# BTB_Mezzanine.net
KiCad netlist of a schematic drawn in Altium Designer
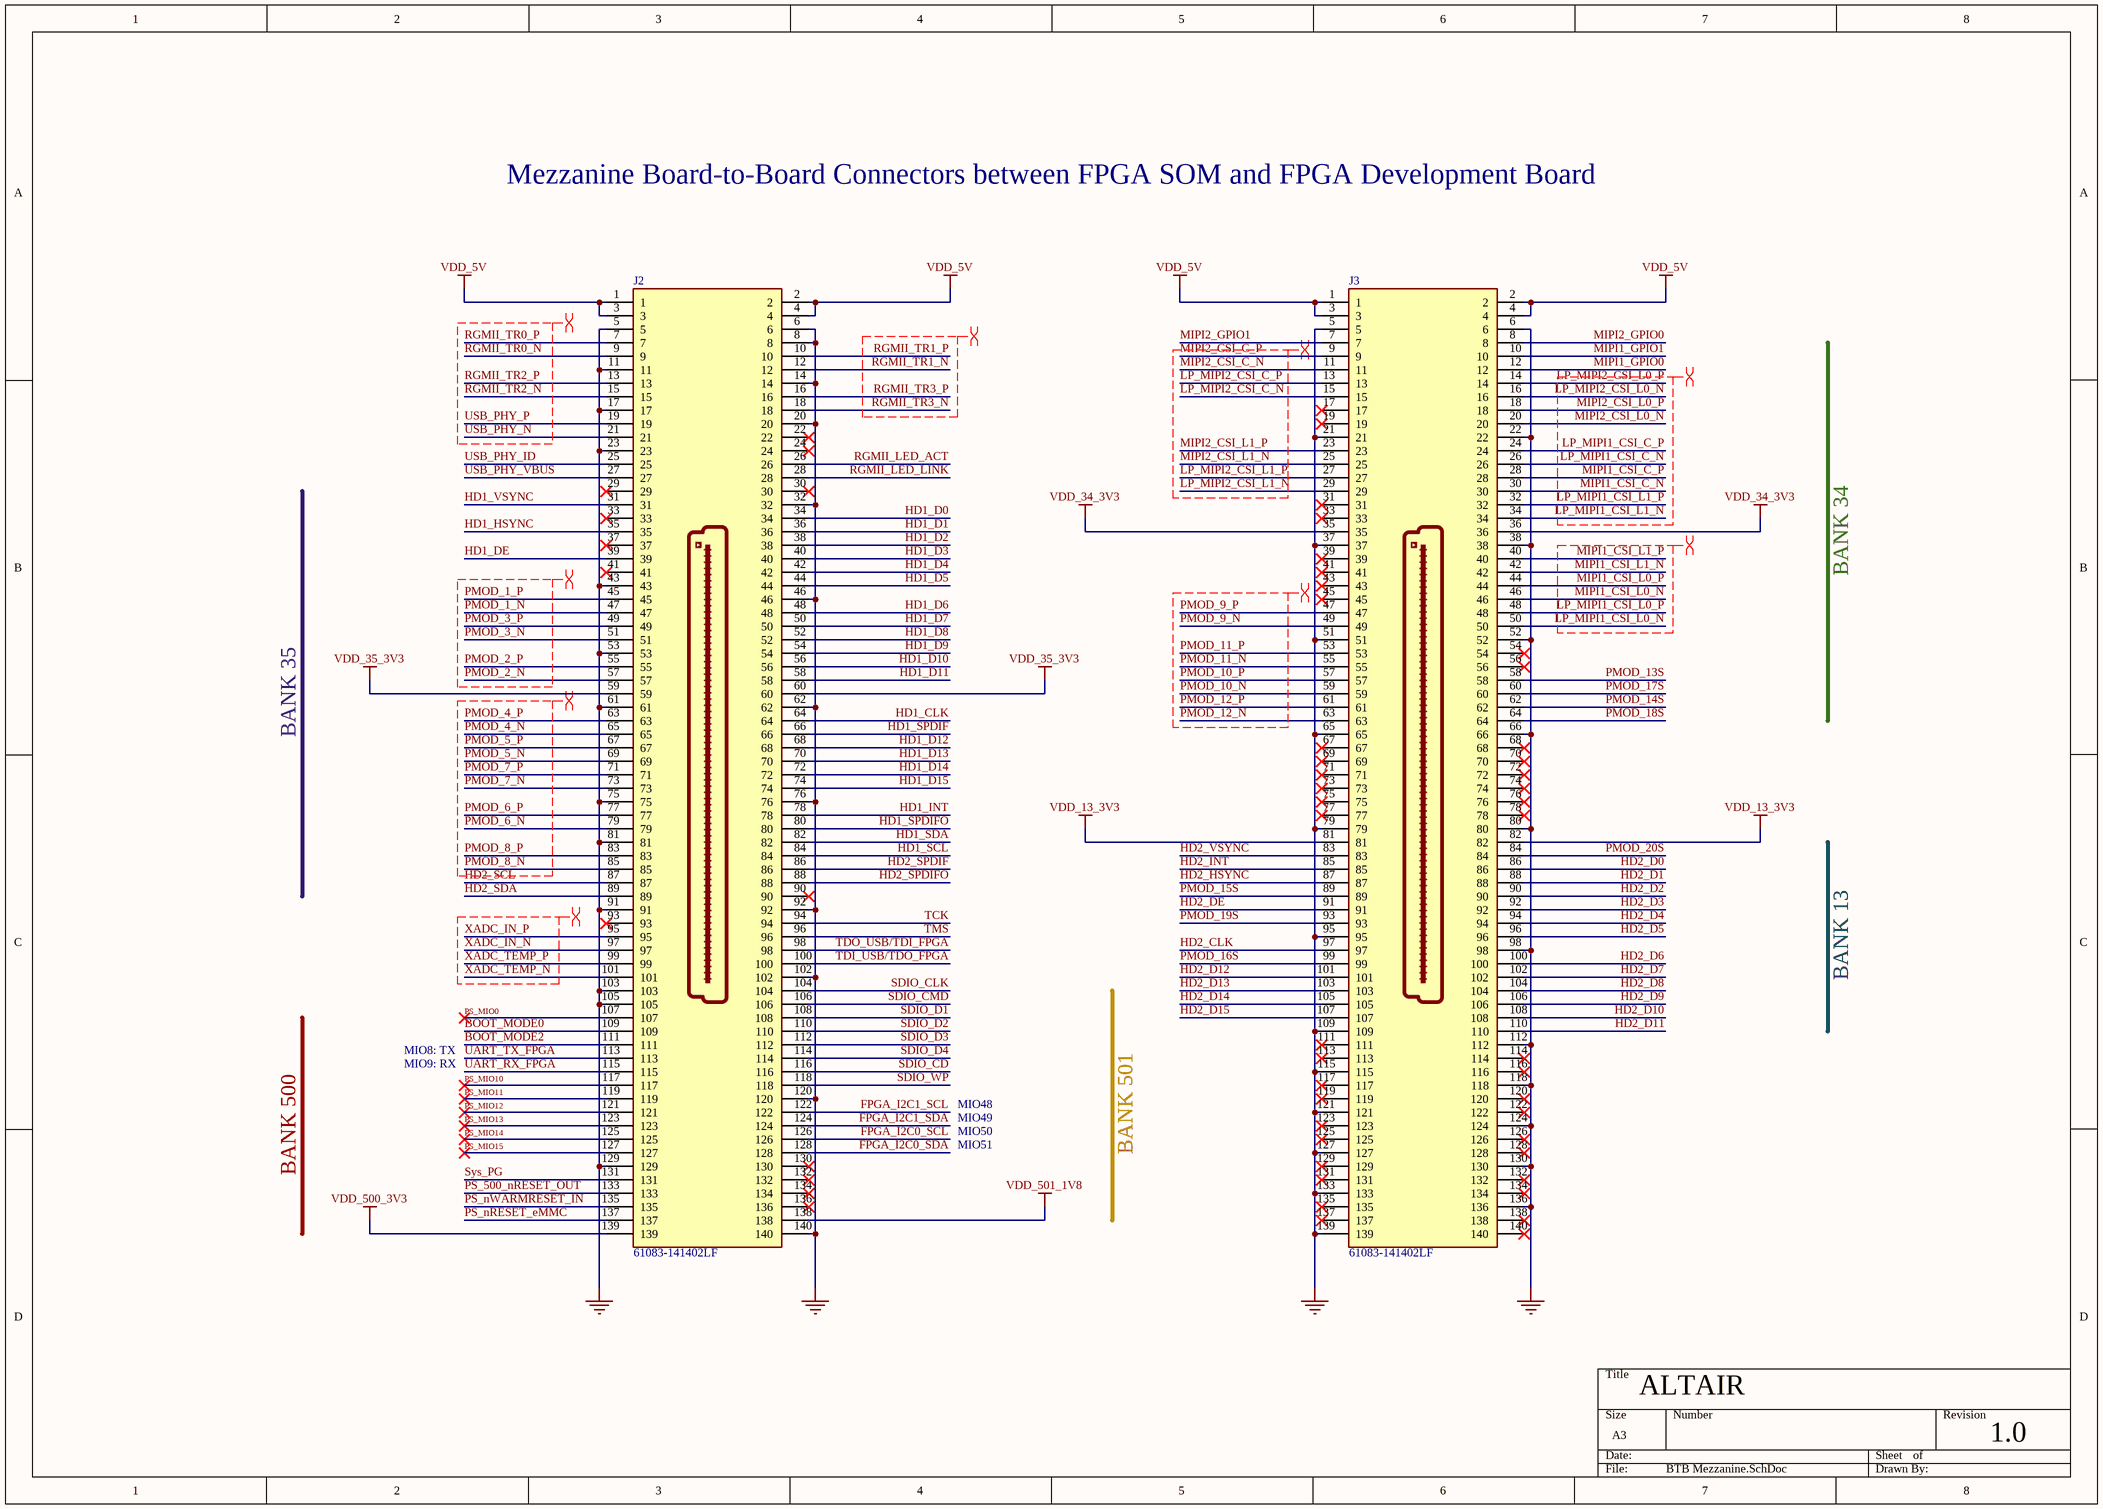
[diagram p0: BTB Mezzanine.SchDoc]

(export (version "E")
  (design (tool "Eeschema 10.0.6"))
  (components
    (comp (ref "J2")
      (value "61083-141402LF")
      (footprint "61083141402LF")
      (description "Connector")
      (fields (field (name "JLCPCB PART #") "C5338666"))
      (libsource (lib "personalGenericLib") (part "61083-141402LF"))
    )
    (comp (ref "J3")
      (value "61083-141402LF")
      (footprint "61083141402LF")
      (description "Connector")
      (fields (field (name "JLCPCB PART #") "C5338666"))
      (libsource (lib "personalGenericLib") (part "61083-141402LF"))
    )
  )
  (nets
    (net (code "1") (name "/BOOT_MODE0") (class "Default")
      (node (ref "J2") (pin "109") (pinfunction "109_109") (pintype "passive"))
    )
    (net (code "2") (name "/BOOT_MODE2") (class "Default")
      (node (ref "J2") (pin "111") (pinfunction "111_111") (pintype "passive"))
    )
    (net (code "3") (name "/FPGA_I2C0_SCL") (class "Default")
      (node (ref "J2") (pin "126") (pinfunction "126_126") (pintype "passive"))
    )
    (net (code "4") (name "/FPGA_I2C0_SDA") (class "Default")
      (node (ref "J2") (pin "128") (pinfunction "128_128") (pintype "passive"))
    )
    (net (code "5") (name "/FPGA_I2C1_SCL") (class "Default")
      (node (ref "J2") (pin "122") (pinfunction "122_122") (pintype "passive"))
    )
    (net (code "6") (name "/FPGA_I2C1_SDA") (class "Default")
      (node (ref "J2") (pin "124") (pinfunction "124_124") (pintype "passive"))
    )
    (net (code "7") (name "/HD1_CLK") (class "Default")
      (node (ref "J2") (pin "64") (pinfunction "64_64") (pintype "passive"))
    )
    (net (code "8") (name "/HD1_D0") (class "Default")
      (node (ref "J2") (pin "34") (pinfunction "34_34") (pintype "passive"))
    )
    (net (code "9") (name "/HD1_D1") (class "Default")
      (node (ref "J2") (pin "36") (pinfunction "36_36") (pintype "passive"))
    )
    (net (code "10") (name "/HD1_D2") (class "Default")
      (node (ref "J2") (pin "38") (pinfunction "38_38") (pintype "passive"))
    )
    (net (code "11") (name "/HD1_D3") (class "Default")
      (node (ref "J2") (pin "40") (pinfunction "40_40") (pintype "passive"))
    )
    (net (code "12") (name "/HD1_D4") (class "Default")
      (node (ref "J2") (pin "42") (pinfunction "42_42") (pintype "passive"))
    )
    (net (code "13") (name "/HD1_D5") (class "Default")
      (node (ref "J2") (pin "44") (pinfunction "44_44") (pintype "passive"))
    )
    (net (code "14") (name "/HD1_D6") (class "Default")
      (node (ref "J2") (pin "48") (pinfunction "48_48") (pintype "passive"))
    )
    (net (code "15") (name "/HD1_D7") (class "Default")
      (node (ref "J2") (pin "50") (pinfunction "50_50") (pintype "passive"))
    )
    (net (code "16") (name "/HD1_D8") (class "Default")
      (node (ref "J2") (pin "52") (pinfunction "52_52") (pintype "passive"))
    )
    (net (code "17") (name "/HD1_D9") (class "Default")
      (node (ref "J2") (pin "54") (pinfunction "54_54") (pintype "passive"))
    )
    (net (code "18") (name "/HD1_D10") (class "Default")
      (node (ref "J2") (pin "56") (pinfunction "56_56") (pintype "passive"))
    )
    (net (code "19") (name "/HD1_D11") (class "Default")
      (node (ref "J2") (pin "58") (pinfunction "58_58") (pintype "passive"))
    )
    (net (code "20") (name "/HD1_D12") (class "Default")
      (node (ref "J2") (pin "68") (pinfunction "68_68") (pintype "passive"))
    )
    (net (code "21") (name "/HD1_D13") (class "Default")
      (node (ref "J2") (pin "70") (pinfunction "70_70") (pintype "passive"))
    )
    (net (code "22") (name "/HD1_D14") (class "Default")
      (node (ref "J2") (pin "72") (pinfunction "72_72") (pintype "passive"))
    )
    (net (code "23") (name "/HD1_D15") (class "Default")
      (node (ref "J2") (pin "74") (pinfunction "74_74") (pintype "passive"))
    )
    (net (code "24") (name "/HD1_DE") (class "Default")
      (node (ref "J2") (pin "39") (pinfunction "39_39") (pintype "passive"))
    )
    (net (code "25") (name "/HD1_HSYNC") (class "Default")
      (node (ref "J2") (pin "35") (pinfunction "35_35") (pintype "passive"))
    )
    (net (code "26") (name "/HD1_INT") (class "Default")
      (node (ref "J2") (pin "78") (pinfunction "78_78") (pintype "passive"))
    )
    (net (code "27") (name "/HD1_SCL") (class "Default")
      (node (ref "J2") (pin "84") (pinfunction "84_84") (pintype "passive"))
    )
    (net (code "28") (name "/HD1_SDA") (class "Default")
      (node (ref "J2") (pin "82") (pinfunction "82_82") (pintype "passive"))
    )
    (net (code "29") (name "/HD1_SPDIF") (class "Default")
      (node (ref "J2") (pin "66") (pinfunction "66_66") (pintype "passive"))
    )
    (net (code "30") (name "/HD1_SPDIFO") (class "Default")
      (node (ref "J2") (pin "80") (pinfunction "80_80") (pintype "passive"))
    )
    (net (code "31") (name "/HD1_VSYNC") (class "Default")
      (node (ref "J2") (pin "31") (pinfunction "31_31") (pintype "passive"))
    )
    (net (code "32") (name "/HD2_CLK") (class "Default")
      (node (ref "J3") (pin "97") (pinfunction "97_97") (pintype "passive"))
    )
    (net (code "33") (name "/HD2_D0") (class "Default")
      (node (ref "J3") (pin "86") (pinfunction "86_86") (pintype "passive"))
    )
    (net (code "34") (name "/HD2_D1") (class "Default")
      (node (ref "J3") (pin "88") (pinfunction "88_88") (pintype "passive"))
    )
    (net (code "35") (name "/HD2_D2") (class "Default")
      (node (ref "J3") (pin "90") (pinfunction "90_90") (pintype "passive"))
    )
    (net (code "36") (name "/HD2_D3") (class "Default")
      (node (ref "J3") (pin "92") (pinfunction "92_92") (pintype "passive"))
    )
    (net (code "37") (name "/HD2_D4") (class "Default")
      (node (ref "J3") (pin "94") (pinfunction "94_94") (pintype "passive"))
    )
    (net (code "38") (name "/HD2_D5") (class "Default")
      (node (ref "J3") (pin "96") (pinfunction "96_96") (pintype "passive"))
    )
    (net (code "39") (name "/HD2_D6") (class "Default")
      (node (ref "J3") (pin "100") (pinfunction "100_100") (pintype "passive"))
    )
    (net (code "40") (name "/HD2_D7") (class "Default")
      (node (ref "J3") (pin "102") (pinfunction "102_102") (pintype "passive"))
    )
    (net (code "41") (name "/HD2_D8") (class "Default")
      (node (ref "J3") (pin "104") (pinfunction "104_104") (pintype "passive"))
    )
    (net (code "42") (name "/HD2_D9") (class "Default")
      (node (ref "J3") (pin "106") (pinfunction "106_106") (pintype "passive"))
    )
    (net (code "43") (name "/HD2_D10") (class "Default")
      (node (ref "J3") (pin "108") (pinfunction "108_108") (pintype "passive"))
    )
    (net (code "44") (name "/HD2_D11") (class "Default")
      (node (ref "J3") (pin "110") (pinfunction "110_110") (pintype "passive"))
    )
    (net (code "45") (name "/HD2_D12") (class "Default")
      (node (ref "J3") (pin "101") (pinfunction "101_101") (pintype "passive"))
    )
    (net (code "46") (name "/HD2_D13") (class "Default")
      (node (ref "J3") (pin "103") (pinfunction "103_103") (pintype "passive"))
    )
    (net (code "47") (name "/HD2_D14") (class "Default")
      (node (ref "J3") (pin "105") (pinfunction "105_105") (pintype "passive"))
    )
    (net (code "48") (name "/HD2_D15") (class "Default")
      (node (ref "J3") (pin "107") (pinfunction "107_107") (pintype "passive"))
    )
    (net (code "49") (name "/HD2_DE") (class "Default")
      (node (ref "J3") (pin "91") (pinfunction "91_91") (pintype "passive"))
    )
    (net (code "50") (name "/HD2_HSYNC") (class "Default")
      (node (ref "J3") (pin "87") (pinfunction "87_87") (pintype "passive"))
    )
    (net (code "51") (name "/HD2_INT") (class "Default")
      (node (ref "J3") (pin "85") (pinfunction "85_85") (pintype "passive"))
    )
    (net (code "52") (name "/HD2_SCL") (class "Default")
      (node (ref "J2") (pin "87") (pinfunction "87_87") (pintype "passive"))
    )
    (net (code "53") (name "/HD2_SDA") (class "Default")
      (node (ref "J2") (pin "89") (pinfunction "89_89") (pintype "passive"))
    )
    (net (code "54") (name "/HD2_SPDIF") (class "Default")
      (node (ref "J2") (pin "86") (pinfunction "86_86") (pintype "passive"))
    )
    (net (code "55") (name "/HD2_SPDIFO") (class "Default")
      (node (ref "J2") (pin "88") (pinfunction "88_88") (pintype "passive"))
    )
    (net (code "56") (name "/HD2_VSYNC") (class "Default")
      (node (ref "J3") (pin "83") (pinfunction "83_83") (pintype "passive"))
    )
    (net (code "57") (name "/LP_MIPI1_CSI_C_N") (class "Default")
      (node (ref "J3") (pin "26") (pinfunction "26_26") (pintype "passive"))
    )
    (net (code "58") (name "/LP_MIPI1_CSI_C_P") (class "Default")
      (node (ref "J3") (pin "24") (pinfunction "24_24") (pintype "passive"))
    )
    (net (code "59") (name "/LP_MIPI1_CSI_L0_N") (class "Default")
      (node (ref "J3") (pin "50") (pinfunction "50_50") (pintype "passive"))
    )
    (net (code "60") (name "/LP_MIPI1_CSI_L0_P") (class "Default")
      (node (ref "J3") (pin "48") (pinfunction "48_48") (pintype "passive"))
    )
    (net (code "61") (name "/LP_MIPI1_CSI_L1_N") (class "Default")
      (node (ref "J3") (pin "34") (pinfunction "34_34") (pintype "passive"))
    )
    (net (code "62") (name "/LP_MIPI1_CSI_L1_P") (class "Default")
      (node (ref "J3") (pin "32") (pinfunction "32_32") (pintype "passive"))
    )
    (net (code "63") (name "/LP_MIPI2_CSI_C_N") (class "Default")
      (node (ref "J3") (pin "15") (pinfunction "15_15") (pintype "passive"))
    )
    (net (code "64") (name "/LP_MIPI2_CSI_C_P") (class "Default")
      (node (ref "J3") (pin "13") (pinfunction "13_13") (pintype "passive"))
    )
    (net (code "65") (name "/LP_MIPI2_CSI_L0_N") (class "Default")
      (node (ref "J3") (pin "16") (pinfunction "16_16") (pintype "passive"))
    )
    (net (code "66") (name "/LP_MIPI2_CSI_L0_P") (class "Default")
      (node (ref "J3") (pin "14") (pinfunction "14_14") (pintype "passive"))
    )
    (net (code "67") (name "/LP_MIPI2_CSI_L1_N") (class "Default")
      (node (ref "J3") (pin "29") (pinfunction "29_29") (pintype "passive"))
    )
    (net (code "68") (name "/LP_MIPI2_CSI_L1_P") (class "Default")
      (node (ref "J3") (pin "27") (pinfunction "27_27") (pintype "passive"))
    )
    (net (code "69") (name "/MIPI1_CSI_C_N") (class "Default")
      (node (ref "J3") (pin "30") (pinfunction "30_30") (pintype "passive"))
    )
    (net (code "70") (name "/MIPI1_CSI_C_P") (class "Default")
      (node (ref "J3") (pin "28") (pinfunction "28_28") (pintype "passive"))
    )
    (net (code "71") (name "/MIPI1_CSI_L0_N") (class "Default")
      (node (ref "J3") (pin "46") (pinfunction "46_46") (pintype "passive"))
    )
    (net (code "72") (name "/MIPI1_CSI_L0_P") (class "Default")
      (node (ref "J3") (pin "44") (pinfunction "44_44") (pintype "passive"))
    )
    (net (code "73") (name "/MIPI1_CSI_L1_N") (class "Default")
      (node (ref "J3") (pin "42") (pinfunction "42_42") (pintype "passive"))
    )
    (net (code "74") (name "/MIPI1_CSI_L1_P") (class "Default")
      (node (ref "J3") (pin "40") (pinfunction "40_40") (pintype "passive"))
    )
    (net (code "75") (name "/MIPI1_GPIO0") (class "Default")
      (node (ref "J3") (pin "12") (pinfunction "12_12") (pintype "passive"))
    )
    (net (code "76") (name "/MIPI1_GPIO1") (class "Default")
      (node (ref "J3") (pin "10") (pinfunction "10_10") (pintype "passive"))
    )
    (net (code "77") (name "/MIPI2_CSI_C_N") (class "Default")
      (node (ref "J3") (pin "11") (pinfunction "11_11") (pintype "passive"))
    )
    (net (code "78") (name "/MIPI2_CSI_C_P") (class "Default")
      (node (ref "J3") (pin "9") (pinfunction "9_9") (pintype "passive"))
    )
    (net (code "79") (name "/MIPI2_CSI_L0_N") (class "Default")
      (node (ref "J3") (pin "20") (pinfunction "20_20") (pintype "passive"))
    )
    (net (code "80") (name "/MIPI2_CSI_L0_P") (class "Default")
      (node (ref "J3") (pin "18") (pinfunction "18_18") (pintype "passive"))
    )
    (net (code "81") (name "/MIPI2_CSI_L1_N") (class "Default")
      (node (ref "J3") (pin "25") (pinfunction "25_25") (pintype "passive"))
    )
    (net (code "82") (name "/MIPI2_CSI_L1_P") (class "Default")
      (node (ref "J3") (pin "23") (pinfunction "23_23") (pintype "passive"))
    )
    (net (code "83") (name "/MIPI2_GPIO0") (class "Default")
      (node (ref "J3") (pin "8") (pinfunction "8_8") (pintype "passive"))
    )
    (net (code "84") (name "/MIPI2_GPIO1") (class "Default")
      (node (ref "J3") (pin "7") (pinfunction "7_7") (pintype "passive"))
    )
    (net (code "85") (name "/PMOD_1_N") (class "Default")
      (node (ref "J2") (pin "47") (pinfunction "47_47") (pintype "passive"))
    )
    (net (code "86") (name "/PMOD_1_P") (class "Default")
      (node (ref "J2") (pin "45") (pinfunction "45_45") (pintype "passive"))
    )
    (net (code "87") (name "/PMOD_2_N") (class "Default")
      (node (ref "J2") (pin "57") (pinfunction "57_57") (pintype "passive"))
    )
    (net (code "88") (name "/PMOD_2_P") (class "Default")
      (node (ref "J2") (pin "55") (pinfunction "55_55") (pintype "passive"))
    )
    (net (code "89") (name "/PMOD_3_N") (class "Default")
      (node (ref "J2") (pin "51") (pinfunction "51_51") (pintype "passive"))
    )
    (net (code "90") (name "/PMOD_3_P") (class "Default")
      (node (ref "J2") (pin "49") (pinfunction "49_49") (pintype "passive"))
    )
    (net (code "91") (name "/PMOD_4_N") (class "Default")
      (node (ref "J2") (pin "65") (pinfunction "65_65") (pintype "passive"))
    )
    (net (code "92") (name "/PMOD_4_P") (class "Default")
      (node (ref "J2") (pin "63") (pinfunction "63_63") (pintype "passive"))
    )
    (net (code "93") (name "/PMOD_5_N") (class "Default")
      (node (ref "J2") (pin "69") (pinfunction "69_69") (pintype "passive"))
    )
    (net (code "94") (name "/PMOD_5_P") (class "Default")
      (node (ref "J2") (pin "67") (pinfunction "67_67") (pintype "passive"))
    )
    (net (code "95") (name "/PMOD_6_N") (class "Default")
      (node (ref "J2") (pin "79") (pinfunction "79_79") (pintype "passive"))
    )
    (net (code "96") (name "/PMOD_6_P") (class "Default")
      (node (ref "J2") (pin "77") (pinfunction "77_77") (pintype "passive"))
    )
    (net (code "97") (name "/PMOD_7_N") (class "Default")
      (node (ref "J2") (pin "73") (pinfunction "73_73") (pintype "passive"))
    )
    (net (code "98") (name "/PMOD_7_P") (class "Default")
      (node (ref "J2") (pin "71") (pinfunction "71_71") (pintype "passive"))
    )
    (net (code "99") (name "/PMOD_8_N") (class "Default")
      (node (ref "J2") (pin "85") (pinfunction "85_85") (pintype "passive"))
    )
    (net (code "100") (name "/PMOD_8_P") (class "Default")
      (node (ref "J2") (pin "83") (pinfunction "83_83") (pintype "passive"))
    )
    (net (code "101") (name "/PMOD_9_N") (class "Default")
      (node (ref "J3") (pin "49") (pinfunction "49_49") (pintype "passive"))
    )
    (net (code "102") (name "/PMOD_9_P") (class "Default")
      (node (ref "J3") (pin "47") (pinfunction "47_47") (pintype "passive"))
    )
    (net (code "103") (name "/PMOD_10_N") (class "Default")
      (node (ref "J3") (pin "59") (pinfunction "59_59") (pintype "passive"))
    )
    (net (code "104") (name "/PMOD_10_P") (class "Default")
      (node (ref "J3") (pin "57") (pinfunction "57_57") (pintype "passive"))
    )
    (net (code "105") (name "/PMOD_11_N") (class "Default")
      (node (ref "J3") (pin "55") (pinfunction "55_55") (pintype "passive"))
    )
    (net (code "106") (name "/PMOD_11_P") (class "Default")
      (node (ref "J3") (pin "53") (pinfunction "53_53") (pintype "passive"))
    )
    (net (code "107") (name "/PMOD_12_N") (class "Default")
      (node (ref "J3") (pin "63") (pinfunction "63_63") (pintype "passive"))
    )
    (net (code "108") (name "/PMOD_12_P") (class "Default")
      (node (ref "J3") (pin "61") (pinfunction "61_61") (pintype "passive"))
    )
    (net (code "109") (name "/PMOD_13S") (class "Default")
      (node (ref "J3") (pin "58") (pinfunction "58_58") (pintype "passive"))
    )
    (net (code "110") (name "/PMOD_14S") (class "Default")
      (node (ref "J3") (pin "62") (pinfunction "62_62") (pintype "passive"))
    )
    (net (code "111") (name "/PMOD_15S") (class "Default")
      (node (ref "J3") (pin "89") (pinfunction "89_89") (pintype "passive"))
    )
    (net (code "112") (name "/PMOD_16S") (class "Default")
      (node (ref "J3") (pin "99") (pinfunction "99_99") (pintype "passive"))
    )
    (net (code "113") (name "/PMOD_17S") (class "Default")
      (node (ref "J3") (pin "60") (pinfunction "60_60") (pintype "passive"))
    )
    (net (code "114") (name "/PMOD_18S") (class "Default")
      (node (ref "J3") (pin "64") (pinfunction "64_64") (pintype "passive"))
    )
    (net (code "115") (name "/PMOD_19S") (class "Default")
      (node (ref "J3") (pin "93") (pinfunction "93_93") (pintype "passive"))
    )
    (net (code "116") (name "/PMOD_20S") (class "Default")
      (node (ref "J3") (pin "84") (pinfunction "84_84") (pintype "passive"))
    )
    (net (code "117") (name "/PS_500_nRESET_OUT") (class "Default")
      (node (ref "J2") (pin "133") (pinfunction "133_133") (pintype "passive"))
    )
    (net (code "118") (name "/PS_MIO0") (class "Default")
      (node (ref "J2") (pin "107") (pinfunction "107_107") (pintype "passive+no_connect"))
    )
    (net (code "119") (name "/PS_MIO10") (class "Default")
      (node (ref "J2") (pin "117") (pinfunction "117_117") (pintype "passive+no_connect"))
    )
    (net (code "120") (name "/PS_MIO11") (class "Default")
      (node (ref "J2") (pin "119") (pinfunction "119_119") (pintype "passive+no_connect"))
    )
    (net (code "121") (name "/PS_MIO12") (class "Default")
      (node (ref "J2") (pin "121") (pinfunction "121_121") (pintype "passive+no_connect"))
    )
    (net (code "122") (name "/PS_MIO13") (class "Default")
      (node (ref "J2") (pin "123") (pinfunction "123_123") (pintype "passive+no_connect"))
    )
    (net (code "123") (name "/PS_MIO14") (class "Default")
      (node (ref "J2") (pin "125") (pinfunction "125_125") (pintype "passive+no_connect"))
    )
    (net (code "124") (name "/PS_MIO15") (class "Default")
      (node (ref "J2") (pin "127") (pinfunction "127_127") (pintype "passive+no_connect"))
    )
    (net (code "125") (name "/PS_nRESET_eMMC") (class "Default")
      (node (ref "J2") (pin "137") (pinfunction "137_137") (pintype "passive"))
    )
    (net (code "126") (name "/PS_nWARMRESET_IN") (class "Default")
      (node (ref "J2") (pin "135") (pinfunction "135_135") (pintype "passive"))
    )
    (net (code "127") (name "/RGMII_LED_ACT") (class "Default")
      (node (ref "J2") (pin "26") (pinfunction "26_26") (pintype "passive"))
    )
    (net (code "128") (name "/RGMII_LED_LINK") (class "Default")
      (node (ref "J2") (pin "28") (pinfunction "28_28") (pintype "passive"))
    )
    (net (code "129") (name "/RGMII_TR0_N") (class "Default")
      (node (ref "J2") (pin "9") (pinfunction "9_9") (pintype "passive"))
    )
    (net (code "130") (name "/RGMII_TR0_P") (class "Default")
      (node (ref "J2") (pin "7") (pinfunction "7_7") (pintype "passive"))
    )
    (net (code "131") (name "/RGMII_TR1_N") (class "Default")
      (node (ref "J2") (pin "12") (pinfunction "12_12") (pintype "passive"))
    )
    (net (code "132") (name "/RGMII_TR1_P") (class "Default")
      (node (ref "J2") (pin "10") (pinfunction "10_10") (pintype "passive"))
    )
    (net (code "133") (name "/RGMII_TR2_N") (class "Default")
      (node (ref "J2") (pin "15") (pinfunction "15_15") (pintype "passive"))
    )
    (net (code "134") (name "/RGMII_TR2_P") (class "Default")
      (node (ref "J2") (pin "13") (pinfunction "13_13") (pintype "passive"))
    )
    (net (code "135") (name "/RGMII_TR3_N") (class "Default")
      (node (ref "J2") (pin "18") (pinfunction "18_18") (pintype "passive"))
    )
    (net (code "136") (name "/RGMII_TR3_P") (class "Default")
      (node (ref "J2") (pin "16") (pinfunction "16_16") (pintype "passive"))
    )
    (net (code "137") (name "/SDIO_CD") (class "Default")
      (node (ref "J2") (pin "116") (pinfunction "116_116") (pintype "passive"))
    )
    (net (code "138") (name "/SDIO_CLK") (class "Default")
      (node (ref "J2") (pin "104") (pinfunction "104_104") (pintype "passive"))
    )
    (net (code "139") (name "/SDIO_CMD") (class "Default")
      (node (ref "J2") (pin "106") (pinfunction "106_106") (pintype "passive"))
    )
    (net (code "140") (name "/SDIO_D1") (class "Default")
      (node (ref "J2") (pin "108") (pinfunction "108_108") (pintype "passive"))
    )
    (net (code "141") (name "/SDIO_D2") (class "Default")
      (node (ref "J2") (pin "110") (pinfunction "110_110") (pintype "passive"))
    )
    (net (code "142") (name "/SDIO_D3") (class "Default")
      (node (ref "J2") (pin "112") (pinfunction "112_112") (pintype "passive"))
    )
    (net (code "143") (name "/SDIO_D4") (class "Default")
      (node (ref "J2") (pin "114") (pinfunction "114_114") (pintype "passive"))
    )
    (net (code "144") (name "/SDIO_WP") (class "Default")
      (node (ref "J2") (pin "118") (pinfunction "118_118") (pintype "passive"))
    )
    (net (code "145") (name "/Sys_PG") (class "Default")
      (node (ref "J2") (pin "131") (pinfunction "131_131") (pintype "passive"))
    )
    (net (code "146") (name "/TCK") (class "Default")
      (node (ref "J2") (pin "94") (pinfunction "94_94") (pintype "passive"))
    )
    (net (code "147") (name "/TDI_USB{slash}TDO_FPGA") (class "Default")
      (node (ref "J2") (pin "100") (pinfunction "100_100") (pintype "passive"))
    )
    (net (code "148") (name "/TDO_USB{slash}TDI_FPGA") (class "Default")
      (node (ref "J2") (pin "98") (pinfunction "98_98") (pintype "passive"))
    )
    (net (code "149") (name "/TMS") (class "Default")
      (node (ref "J2") (pin "96") (pinfunction "96_96") (pintype "passive"))
    )
    (net (code "150") (name "/UART_RX_FPGA") (class "Default")
      (node (ref "J2") (pin "115") (pinfunction "115_115") (pintype "passive"))
    )
    (net (code "151") (name "/UART_TX_FPGA") (class "Default")
      (node (ref "J2") (pin "113") (pinfunction "113_113") (pintype "passive"))
    )
    (net (code "152") (name "/USB_PHY_ID") (class "Default")
      (node (ref "J2") (pin "25") (pinfunction "25_25") (pintype "passive"))
    )
    (net (code "153") (name "/USB_PHY_N") (class "Default")
      (node (ref "J2") (pin "21") (pinfunction "21_21") (pintype "passive"))
    )
    (net (code "154") (name "/USB_PHY_P") (class "Default")
      (node (ref "J2") (pin "19") (pinfunction "19_19") (pintype "passive"))
    )
    (net (code "155") (name "/USB_PHY_VBUS") (class "Default")
      (node (ref "J2") (pin "27") (pinfunction "27_27") (pintype "passive"))
    )
    (net (code "156") (name "/XADC_IN_N") (class "Default")
      (node (ref "J2") (pin "97") (pinfunction "97_97") (pintype "passive"))
    )
    (net (code "157") (name "/XADC_IN_P") (class "Default")
      (node (ref "J2") (pin "95") (pinfunction "95_95") (pintype "passive"))
    )
    (net (code "158") (name "/XADC_TEMP_N") (class "Default")
      (node (ref "J2") (pin "101") (pinfunction "101_101") (pintype "passive"))
    )
    (net (code "159") (name "/XADC_TEMP_P") (class "Default")
      (node (ref "J2") (pin "99") (pinfunction "99_99") (pintype "passive"))
    )
    (net (code "160") (name "GND") (class "Default")
      (node (ref "J2") (pin "102") (pinfunction "102_102") (pintype "passive"))
      (node (ref "J2") (pin "103") (pinfunction "103_103") (pintype "passive"))
      (node (ref "J2") (pin "105") (pinfunction "105_105") (pintype "passive"))
      (node (ref "J2") (pin "11") (pinfunction "11_11") (pintype "passive"))
      (node (ref "J2") (pin "120") (pinfunction "120_120") (pintype "passive"))
      (node (ref "J2") (pin "129") (pinfunction "129_129") (pintype "passive"))
      (node (ref "J2") (pin "14") (pinfunction "14_14") (pintype "passive"))
      (node (ref "J2") (pin "140") (pinfunction "140_140") (pintype "passive"))
      (node (ref "J2") (pin "17") (pinfunction "17_17") (pintype "passive"))
      (node (ref "J2") (pin "20") (pinfunction "20_20") (pintype "passive"))
      (node (ref "J2") (pin "23") (pinfunction "23_23") (pintype "passive"))
      (node (ref "J2") (pin "32") (pinfunction "32_32") (pintype "passive"))
      (node (ref "J2") (pin "43") (pinfunction "43_43") (pintype "passive"))
      (node (ref "J2") (pin "46") (pinfunction "46_46") (pintype "passive"))
      (node (ref "J2") (pin "5") (pinfunction "5_5") (pintype "passive"))
      (node (ref "J2") (pin "53") (pinfunction "53_53") (pintype "passive"))
      (node (ref "J2") (pin "6") (pinfunction "6_6") (pintype "passive"))
      (node (ref "J2") (pin "61") (pinfunction "61_61") (pintype "passive"))
      (node (ref "J2") (pin "62") (pinfunction "62_62") (pintype "passive"))
      (node (ref "J2") (pin "75") (pinfunction "75_75") (pintype "passive"))
      (node (ref "J2") (pin "76") (pinfunction "76_76") (pintype "passive"))
      (node (ref "J2") (pin "8") (pinfunction "8_8") (pintype "passive"))
      (node (ref "J2") (pin "81") (pinfunction "81_81") (pintype "passive"))
      (node (ref "J2") (pin "91") (pinfunction "91_91") (pintype "passive"))
      (node (ref "J2") (pin "92") (pinfunction "92_92") (pintype "passive"))
      (node (ref "J3") (pin "109") (pinfunction "109_109") (pintype "passive"))
      (node (ref "J3") (pin "112") (pinfunction "112_112") (pintype "passive"))
      (node (ref "J3") (pin "115") (pinfunction "115_115") (pintype "passive"))
      (node (ref "J3") (pin "118") (pinfunction "118_118") (pintype "passive"))
      (node (ref "J3") (pin "121") (pinfunction "121_121") (pintype "passive"))
      (node (ref "J3") (pin "124") (pinfunction "124_124") (pintype "passive"))
      (node (ref "J3") (pin "127") (pinfunction "127_127") (pintype "passive"))
      (node (ref "J3") (pin "130") (pinfunction "130_130") (pintype "passive"))
      (node (ref "J3") (pin "133") (pinfunction "133_133") (pintype "passive"))
      (node (ref "J3") (pin "136") (pinfunction "136_136") (pintype "passive"))
      (node (ref "J3") (pin "139") (pinfunction "139_139") (pintype "passive"))
      (node (ref "J3") (pin "21") (pinfunction "21_21") (pintype "passive"))
      (node (ref "J3") (pin "22") (pinfunction "22_22") (pintype "passive"))
      (node (ref "J3") (pin "37") (pinfunction "37_37") (pintype "passive"))
      (node (ref "J3") (pin "38") (pinfunction "38_38") (pintype "passive"))
      (node (ref "J3") (pin "5") (pinfunction "5_5") (pintype "passive"))
      (node (ref "J3") (pin "51") (pinfunction "51_51") (pintype "passive"))
      (node (ref "J3") (pin "52") (pinfunction "52_52") (pintype "passive"))
      (node (ref "J3") (pin "6") (pinfunction "6_6") (pintype "passive"))
      (node (ref "J3") (pin "65") (pinfunction "65_65") (pintype "passive"))
      (node (ref "J3") (pin "66") (pinfunction "66_66") (pintype "passive"))
      (node (ref "J3") (pin "79") (pinfunction "79_79") (pintype "passive"))
      (node (ref "J3") (pin "80") (pinfunction "80_80") (pintype "passive"))
      (node (ref "J3") (pin "95") (pinfunction "95_95") (pintype "passive"))
      (node (ref "J3") (pin "98") (pinfunction "98_98") (pintype "passive"))
    )
    (net (code "161") (name "VDD_5V") (class "Default")
      (node (ref "J2") (pin "1") (pinfunction "1_1") (pintype "passive"))
      (node (ref "J2") (pin "2") (pinfunction "2_2") (pintype "passive"))
      (node (ref "J2") (pin "3") (pinfunction "3_3") (pintype "passive"))
      (node (ref "J2") (pin "4") (pinfunction "4_4") (pintype "passive"))
      (node (ref "J3") (pin "1") (pinfunction "1_1") (pintype "passive"))
      (node (ref "J3") (pin "2") (pinfunction "2_2") (pintype "passive"))
      (node (ref "J3") (pin "3") (pinfunction "3_3") (pintype "passive"))
      (node (ref "J3") (pin "4") (pinfunction "4_4") (pintype "passive"))
    )
    (net (code "162") (name "VDD_13_3V3") (class "Default")
      (node (ref "J3") (pin "81") (pinfunction "81_81") (pintype "passive"))
      (node (ref "J3") (pin "82") (pinfunction "82_82") (pintype "passive"))
    )
    (net (code "163") (name "VDD_34_3V3") (class "Default")
      (node (ref "J3") (pin "35") (pinfunction "35_35") (pintype "passive"))
      (node (ref "J3") (pin "36") (pinfunction "36_36") (pintype "passive"))
    )
    (net (code "164") (name "VDD_35_3V3") (class "Default")
      (node (ref "J2") (pin "59") (pinfunction "59_59") (pintype "passive"))
      (node (ref "J2") (pin "60") (pinfunction "60_60") (pintype "passive"))
    )
    (net (code "165") (name "VDD_500_3V3") (class "Default")
      (node (ref "J2") (pin "139") (pinfunction "139_139") (pintype "passive"))
    )
    (net (code "166") (name "VDD_501_1V8") (class "Default")
      (node (ref "J2") (pin "138") (pinfunction "138_138") (pintype "passive"))
    )
    (net (code "167") (name "unconnected-(J2-Pad22)") (class "Default")
      (node (ref "J2") (pin "22") (pinfunction "22_22") (pintype "passive+no_connect"))
    )
    (net (code "168") (name "unconnected-(J2-Pad24)") (class "Default")
      (node (ref "J2") (pin "24") (pinfunction "24_24") (pintype "passive+no_connect"))
    )
    (net (code "169") (name "unconnected-(J2-Pad29)") (class "Default")
      (node (ref "J2") (pin "29") (pinfunction "29_29") (pintype "passive+no_connect"))
    )
    (net (code "170") (name "unconnected-(J2-Pad30)") (class "Default")
      (node (ref "J2") (pin "30") (pinfunction "30_30") (pintype "passive+no_connect"))
    )
    (net (code "171") (name "unconnected-(J2-Pad33)") (class "Default")
      (node (ref "J2") (pin "33") (pinfunction "33_33") (pintype "passive+no_connect"))
    )
    (net (code "172") (name "unconnected-(J2-Pad37)") (class "Default")
      (node (ref "J2") (pin "37") (pinfunction "37_37") (pintype "passive+no_connect"))
    )
    (net (code "173") (name "unconnected-(J2-Pad41)") (class "Default")
      (node (ref "J2") (pin "41") (pinfunction "41_41") (pintype "passive+no_connect"))
    )
    (net (code "174") (name "unconnected-(J2-Pad90)") (class "Default")
      (node (ref "J2") (pin "90") (pinfunction "90_90") (pintype "passive+no_connect"))
    )
    (net (code "175") (name "unconnected-(J2-Pad93)") (class "Default")
      (node (ref "J2") (pin "93") (pinfunction "93_93") (pintype "passive+no_connect"))
    )
    (net (code "176") (name "unconnected-(J2-Pad130)") (class "Default")
      (node (ref "J2") (pin "130") (pinfunction "130_130") (pintype "passive+no_connect"))
    )
    (net (code "177") (name "unconnected-(J2-Pad132)") (class "Default")
      (node (ref "J2") (pin "132") (pinfunction "132_132") (pintype "passive+no_connect"))
    )
    (net (code "178") (name "unconnected-(J2-Pad134)") (class "Default")
      (node (ref "J2") (pin "134") (pinfunction "134_134") (pintype "passive+no_connect"))
    )
    (net (code "179") (name "unconnected-(J2-Pad136)") (class "Default")
      (node (ref "J2") (pin "136") (pinfunction "136_136") (pintype "passive+no_connect"))
    )
    (net (code "180") (name "unconnected-(J3-Pad17)") (class "Default")
      (node (ref "J3") (pin "17") (pinfunction "17_17") (pintype "passive+no_connect"))
    )
    (net (code "181") (name "unconnected-(J3-Pad19)") (class "Default")
      (node (ref "J3") (pin "19") (pinfunction "19_19") (pintype "passive+no_connect"))
    )
    (net (code "182") (name "unconnected-(J3-Pad31)") (class "Default")
      (node (ref "J3") (pin "31") (pinfunction "31_31") (pintype "passive+no_connect"))
    )
    (net (code "183") (name "unconnected-(J3-Pad33)") (class "Default")
      (node (ref "J3") (pin "33") (pinfunction "33_33") (pintype "passive+no_connect"))
    )
    (net (code "184") (name "unconnected-(J3-Pad39)") (class "Default")
      (node (ref "J3") (pin "39") (pinfunction "39_39") (pintype "passive+no_connect"))
    )
    (net (code "185") (name "unconnected-(J3-Pad41)") (class "Default")
      (node (ref "J3") (pin "41") (pinfunction "41_41") (pintype "passive+no_connect"))
    )
    (net (code "186") (name "unconnected-(J3-Pad43)") (class "Default")
      (node (ref "J3") (pin "43") (pinfunction "43_43") (pintype "passive+no_connect"))
    )
    (net (code "187") (name "unconnected-(J3-Pad45)") (class "Default")
      (node (ref "J3") (pin "45") (pinfunction "45_45") (pintype "passive+no_connect"))
    )
    (net (code "188") (name "unconnected-(J3-Pad54)") (class "Default")
      (node (ref "J3") (pin "54") (pinfunction "54_54") (pintype "passive+no_connect"))
    )
    (net (code "189") (name "unconnected-(J3-Pad56)") (class "Default")
      (node (ref "J3") (pin "56") (pinfunction "56_56") (pintype "passive+no_connect"))
    )
    (net (code "190") (name "unconnected-(J3-Pad67)") (class "Default")
      (node (ref "J3") (pin "67") (pinfunction "67_67") (pintype "passive+no_connect"))
    )
    (net (code "191") (name "unconnected-(J3-Pad68)") (class "Default")
      (node (ref "J3") (pin "68") (pinfunction "68_68") (pintype "passive+no_connect"))
    )
    (net (code "192") (name "unconnected-(J3-Pad69)") (class "Default")
      (node (ref "J3") (pin "69") (pinfunction "69_69") (pintype "passive+no_connect"))
    )
    (net (code "193") (name "unconnected-(J3-Pad70)") (class "Default")
      (node (ref "J3") (pin "70") (pinfunction "70_70") (pintype "passive+no_connect"))
    )
    (net (code "194") (name "unconnected-(J3-Pad71)") (class "Default")
      (node (ref "J3") (pin "71") (pinfunction "71_71") (pintype "passive+no_connect"))
    )
    (net (code "195") (name "unconnected-(J3-Pad72)") (class "Default")
      (node (ref "J3") (pin "72") (pinfunction "72_72") (pintype "passive+no_connect"))
    )
    (net (code "196") (name "unconnected-(J3-Pad73)") (class "Default")
      (node (ref "J3") (pin "73") (pinfunction "73_73") (pintype "passive+no_connect"))
    )
    (net (code "197") (name "unconnected-(J3-Pad74)") (class "Default")
      (node (ref "J3") (pin "74") (pinfunction "74_74") (pintype "passive+no_connect"))
    )
    (net (code "198") (name "unconnected-(J3-Pad75)") (class "Default")
      (node (ref "J3") (pin "75") (pinfunction "75_75") (pintype "passive+no_connect"))
    )
    (net (code "199") (name "unconnected-(J3-Pad76)") (class "Default")
      (node (ref "J3") (pin "76") (pinfunction "76_76") (pintype "passive+no_connect"))
    )
    (net (code "200") (name "unconnected-(J3-Pad77)") (class "Default")
      (node (ref "J3") (pin "77") (pinfunction "77_77") (pintype "passive+no_connect"))
    )
    (net (code "201") (name "unconnected-(J3-Pad78)") (class "Default")
      (node (ref "J3") (pin "78") (pinfunction "78_78") (pintype "passive+no_connect"))
    )
    (net (code "202") (name "unconnected-(J3-Pad111)") (class "Default")
      (node (ref "J3") (pin "111") (pinfunction "111_111") (pintype "passive+no_connect"))
    )
    (net (code "203") (name "unconnected-(J3-Pad113)") (class "Default")
      (node (ref "J3") (pin "113") (pinfunction "113_113") (pintype "passive+no_connect"))
    )
    (net (code "204") (name "unconnected-(J3-Pad114)") (class "Default")
      (node (ref "J3") (pin "114") (pinfunction "114_114") (pintype "passive+no_connect"))
    )
    (net (code "205") (name "unconnected-(J3-Pad116)") (class "Default")
      (node (ref "J3") (pin "116") (pinfunction "116_116") (pintype "passive+no_connect"))
    )
    (net (code "206") (name "unconnected-(J3-Pad117)") (class "Default")
      (node (ref "J3") (pin "117") (pinfunction "117_117") (pintype "passive+no_connect"))
    )
    (net (code "207") (name "unconnected-(J3-Pad119)") (class "Default")
      (node (ref "J3") (pin "119") (pinfunction "119_119") (pintype "passive+no_connect"))
    )
    (net (code "208") (name "unconnected-(J3-Pad120)") (class "Default")
      (node (ref "J3") (pin "120") (pinfunction "120_120") (pintype "passive+no_connect"))
    )
    (net (code "209") (name "unconnected-(J3-Pad122)") (class "Default")
      (node (ref "J3") (pin "122") (pinfunction "122_122") (pintype "passive+no_connect"))
    )
    (net (code "210") (name "unconnected-(J3-Pad123)") (class "Default")
      (node (ref "J3") (pin "123") (pinfunction "123_123") (pintype "passive+no_connect"))
    )
    (net (code "211") (name "unconnected-(J3-Pad125)") (class "Default")
      (node (ref "J3") (pin "125") (pinfunction "125_125") (pintype "passive+no_connect"))
    )
    (net (code "212") (name "unconnected-(J3-Pad126)") (class "Default")
      (node (ref "J3") (pin "126") (pinfunction "126_126") (pintype "passive+no_connect"))
    )
    (net (code "213") (name "unconnected-(J3-Pad128)") (class "Default")
      (node (ref "J3") (pin "128") (pinfunction "128_128") (pintype "passive+no_connect"))
    )
    (net (code "214") (name "unconnected-(J3-Pad129)") (class "Default")
      (node (ref "J3") (pin "129") (pinfunction "129_129") (pintype "passive+no_connect"))
    )
    (net (code "215") (name "unconnected-(J3-Pad131)") (class "Default")
      (node (ref "J3") (pin "131") (pinfunction "131_131") (pintype "passive+no_connect"))
    )
    (net (code "216") (name "unconnected-(J3-Pad132)") (class "Default")
      (node (ref "J3") (pin "132") (pinfunction "132_132") (pintype "passive+no_connect"))
    )
    (net (code "217") (name "unconnected-(J3-Pad134)") (class "Default")
      (node (ref "J3") (pin "134") (pinfunction "134_134") (pintype "passive+no_connect"))
    )
    (net (code "218") (name "unconnected-(J3-Pad135)") (class "Default")
      (node (ref "J3") (pin "135") (pinfunction "135_135") (pintype "passive+no_connect"))
    )
    (net (code "219") (name "unconnected-(J3-Pad137)") (class "Default")
      (node (ref "J3") (pin "137") (pinfunction "137_137") (pintype "passive+no_connect"))
    )
    (net (code "220") (name "unconnected-(J3-Pad138)") (class "Default")
      (node (ref "J3") (pin "138") (pinfunction "138_138") (pintype "passive+no_connect"))
    )
    (net (code "221") (name "unconnected-(J3-Pad140)") (class "Default")
      (node (ref "J3") (pin "140") (pinfunction "140_140") (pintype "passive+no_connect"))
    )
  )
)
